# machine_io.net
KiCad netlist of a schematic drawn in Altium Designer
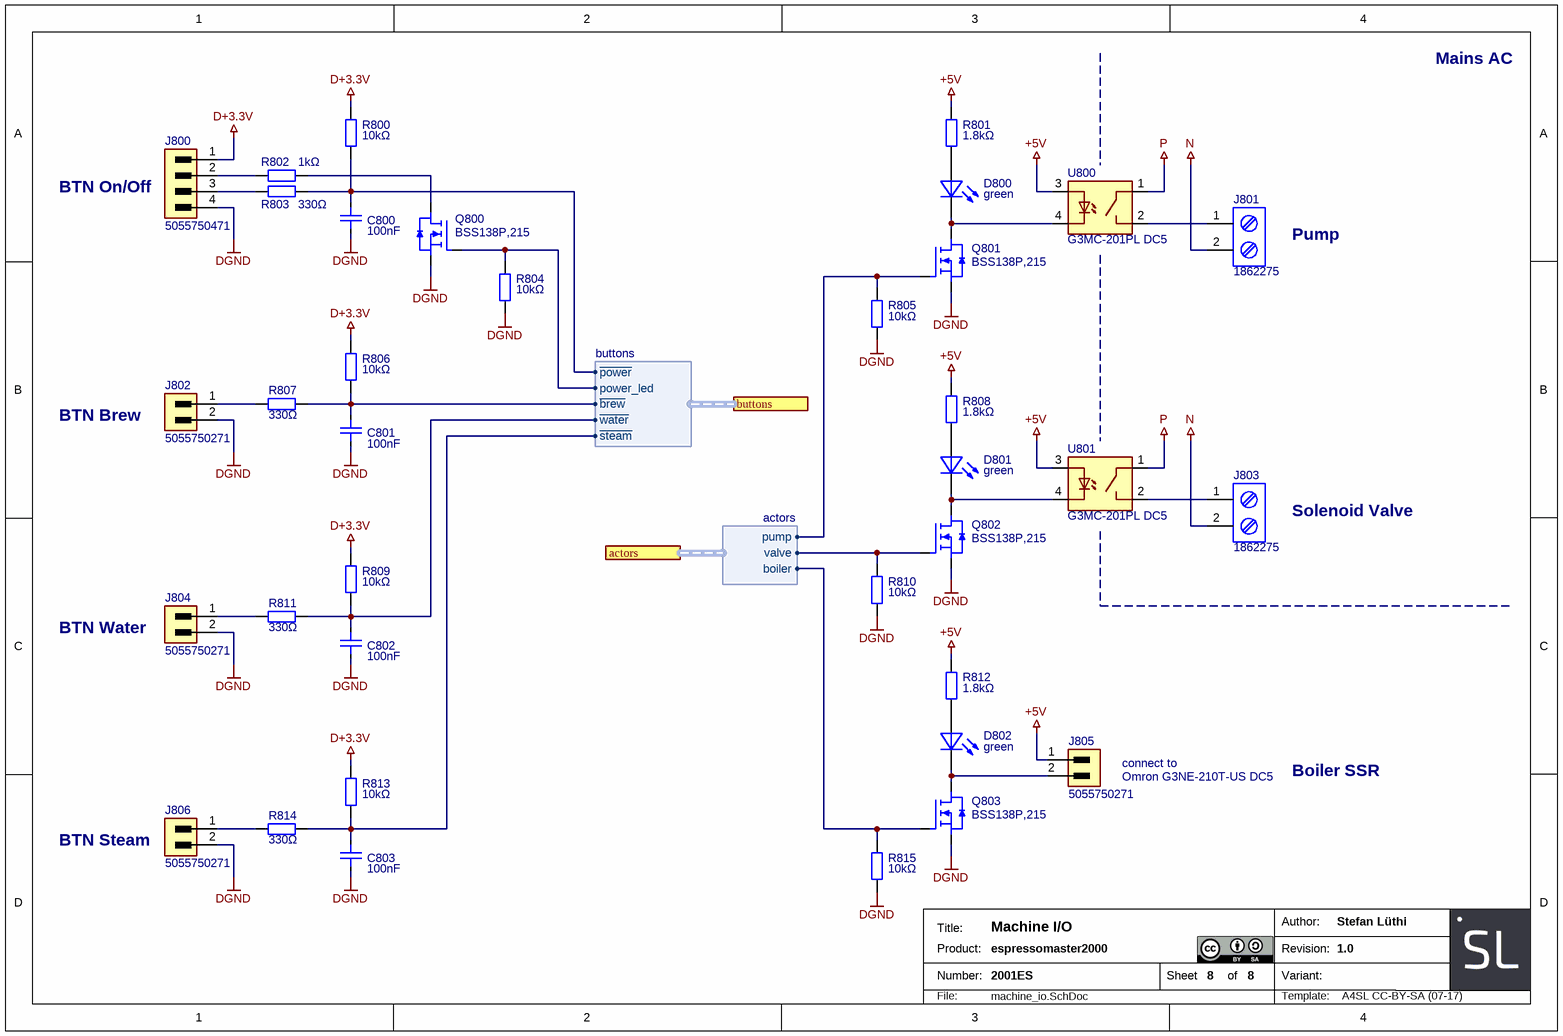
[diagram p0: machine_io.SchDoc]

(export (version "E")
  (design (tool "Eeschema 10.0.6"))
  (components
    (comp (ref "C800")
      (value "100nF")
      (footprint "SMD0603CAP")
      (description "Ceramic Capacitor")
      (libsource (lib "SL-Library") (part "Capacitor Ceramic"))
    )
    (comp (ref "C801")
      (value "100nF")
      (footprint "SMD0603CAP")
      (description "Ceramic Capacitor")
      (libsource (lib "SL-Library") (part "Capacitor Ceramic"))
    )
    (comp (ref "C802")
      (value "100nF")
      (footprint "SMD0603CAP")
      (description "Ceramic Capacitor")
      (libsource (lib "SL-Library") (part "Capacitor Ceramic"))
    )
    (comp (ref "C803")
      (value "100nF")
      (footprint "SMD0603CAP")
      (description "Ceramic Capacitor")
      (libsource (lib "SL-Library") (part "Capacitor Ceramic"))
    )
    (comp (ref "D800")
      (value "green")
      (footprint "SMD0603LED")
      (description "LED")
      (libsource (lib "SL-Library") (part "LED"))
    )
    (comp (ref "D801")
      (value "green")
      (footprint "SMD0603LED")
      (description "LED")
      (libsource (lib "SL-Library") (part "LED"))
    )
    (comp (ref "D802")
      (value "green")
      (footprint "SMD0603LED")
      (description "LED")
      (libsource (lib "SL-Library") (part "LED"))
    )
    (comp (ref "J800")
      (value "5055750471")
      (footprint "5055750471")
      (description "Connector 4x1P")
      (libsource (lib "SL-Library") (part "Connector 4x1P"))
    )
    (comp (ref "J801")
      (value "1862275")
      (footprint "1862275")
      (description "Screw Terminal, 2 Position, 5mm Spacing")
      (libsource (lib "SL-Library") (part "1862275"))
    )
    (comp (ref "J802")
      (value "5055750271")
      (footprint "5055750271")
      (description "Connector 2x1P")
      (libsource (lib "SL-Library") (part "Connector 2x1P"))
    )
    (comp (ref "J803")
      (value "1862275")
      (footprint "1862275")
      (description "Screw Terminal, 2 Position, 5mm Spacing")
      (libsource (lib "SL-Library") (part "1862275"))
    )
    (comp (ref "J804")
      (value "5055750271")
      (footprint "5055750271")
      (description "Connector 2x1P")
      (libsource (lib "SL-Library") (part "Connector 2x1P"))
    )
    (comp (ref "J805")
      (value "5055750271")
      (footprint "5055750271")
      (description "Connector 2x1P")
      (libsource (lib "") (part "Connector 2x1P_1"))
    )
    (comp (ref "J806")
      (value "5055750271")
      (footprint "5055750271")
      (description "Connector 2x1P")
      (libsource (lib "SL-Library") (part "Connector 2x1P"))
    )
    (comp (ref "Q800")
      (value "BSS138P,215")
      (footprint "SOT-23-FET")
      (description "NMOS Transistor")
      (libsource (lib "SL-Library") (part "NMOS"))
    )
    (comp (ref "Q801")
      (value "BSS138P,215")
      (footprint "SOT-23-FET")
      (description "NMOS Transistor")
      (libsource (lib "SL-Library") (part "NMOS"))
    )
    (comp (ref "Q802")
      (value "BSS138P,215")
      (footprint "SOT-23-FET")
      (description "NMOS Transistor")
      (libsource (lib "SL-Library") (part "NMOS"))
    )
    (comp (ref "Q803")
      (value "BSS138P,215")
      (footprint "SOT-23-FET")
      (description "NMOS Transistor")
      (libsource (lib "SL-Library") (part "NMOS"))
    )
    (comp (ref "R800")
      (value "10kΩ")
      (footprint "SMD0603RES")
      (description "Resistor")
      (libsource (lib "SL-Library") (part "Resistor"))
    )
    (comp (ref "R801")
      (value "1.8kΩ")
      (footprint "SMD0603RES")
      (description "Resistor")
      (libsource (lib "SL-Library") (part "Resistor"))
    )
    (comp (ref "R802")
      (value "1kΩ")
      (footprint "SMD0603RES")
      (description "Resistor")
      (libsource (lib "") (part "Resistor_2"))
    )
    (comp (ref "R803")
      (value "330Ω")
      (footprint "SMD0603RES")
      (description "Resistor")
      (libsource (lib "") (part "Resistor_1"))
    )
    (comp (ref "R804")
      (value "10kΩ")
      (footprint "SMD0603RES")
      (description "Resistor")
      (libsource (lib "") (part "Resistor_1"))
    )
    (comp (ref "R805")
      (value "10kΩ")
      (footprint "SMD0603RES")
      (description "Resistor")
      (libsource (lib "") (part "Resistor_2"))
    )
    (comp (ref "R806")
      (value "10kΩ")
      (footprint "SMD0603RES")
      (description "Resistor")
      (libsource (lib "SL-Library") (part "Resistor"))
    )
    (comp (ref "R807")
      (value "330Ω")
      (footprint "SMD0603RES")
      (description "Resistor")
      (libsource (lib "") (part "Resistor_1"))
    )
    (comp (ref "R808")
      (value "1.8kΩ")
      (footprint "SMD0603RES")
      (description "Resistor")
      (libsource (lib "SL-Library") (part "Resistor"))
    )
    (comp (ref "R809")
      (value "10kΩ")
      (footprint "SMD0603RES")
      (description "Resistor")
      (libsource (lib "SL-Library") (part "Resistor"))
    )
    (comp (ref "R810")
      (value "10kΩ")
      (footprint "SMD0603RES")
      (description "Resistor")
      (libsource (lib "") (part "Resistor_2"))
    )
    (comp (ref "R811")
      (value "330Ω")
      (footprint "SMD0603RES")
      (description "Resistor")
      (libsource (lib "") (part "Resistor_1"))
    )
    (comp (ref "R812")
      (value "1.8kΩ")
      (footprint "SMD0603RES")
      (description "Resistor")
      (libsource (lib "SL-Library") (part "Resistor"))
    )
    (comp (ref "R813")
      (value "10kΩ")
      (footprint "SMD0603RES")
      (description "Resistor")
      (libsource (lib "SL-Library") (part "Resistor"))
    )
    (comp (ref "R814")
      (value "330Ω")
      (footprint "SMD0603RES")
      (description "Resistor")
      (libsource (lib "") (part "Resistor_1"))
    )
    (comp (ref "R815")
      (value "10kΩ")
      (footprint "SMD0603RES")
      (description "Resistor")
      (libsource (lib "") (part "Resistor_2"))
    )
    (comp (ref "U800")
      (value "G3MC-201PL DC5")
      (footprint "G3MC-202P")
      (description "OptoMOS Solid State Relay")
      (libsource (lib "SL-Library") (part "OptoMOS SSR"))
    )
    (comp (ref "U801")
      (value "G3MC-201PL DC5")
      (footprint "G3MC-202P")
      (description "OptoMOS Solid State Relay")
      (libsource (lib "SL-Library") (part "OptoMOS SSR"))
    )
  )
  (nets
    (net (code "3") (name "+5V") (class "Default")
      (node (ref "J805") (pin "1") (pinfunction "1_1") (pintype "passive"))
      (node (ref "R801") (pin "2") (pinfunction "2_2") (pintype "passive"))
      (node (ref "R808") (pin "2") (pinfunction "2_2") (pintype "passive"))
      (node (ref "R812") (pin "2") (pinfunction "2_2") (pintype "passive"))
      (node (ref "U800") (pin "3") (pinfunction "3_3") (pintype "passive"))
      (node (ref "U801") (pin "3") (pinfunction "3_3") (pintype "passive"))
    )
    (net (code "6") (name "D+3.3V") (class "Default")
      (node (ref "J800") (pin "1") (pinfunction "1_1") (pintype "passive"))
      (node (ref "R800") (pin "2") (pinfunction "2_2") (pintype "passive"))
      (node (ref "R806") (pin "2") (pinfunction "2_2") (pintype "passive"))
      (node (ref "R809") (pin "2") (pinfunction "2_2") (pintype "passive"))
      (node (ref "R813") (pin "2") (pinfunction "2_2") (pintype "passive"))
    )
    (net (code "7") (name "DGND") (class "Default")
      (node (ref "C800") (pin "2") (pinfunction "2_2") (pintype "passive"))
      (node (ref "C801") (pin "2") (pinfunction "2_2") (pintype "passive"))
      (node (ref "C802") (pin "2") (pinfunction "2_2") (pintype "passive"))
      (node (ref "C803") (pin "2") (pinfunction "2_2") (pintype "passive"))
      (node (ref "J800") (pin "4") (pinfunction "4_4") (pintype "passive"))
      (node (ref "J802") (pin "2") (pinfunction "2_2") (pintype "passive"))
      (node (ref "J804") (pin "2") (pinfunction "2_2") (pintype "passive"))
      (node (ref "J806") (pin "2") (pinfunction "2_2") (pintype "passive"))
      (node (ref "Q800") (pin "S") (pinfunction "S_S") (pintype "passive"))
      (node (ref "Q801") (pin "S") (pinfunction "S_S") (pintype "passive"))
      (node (ref "Q802") (pin "S") (pinfunction "S_S") (pintype "passive"))
      (node (ref "Q803") (pin "S") (pinfunction "S_S") (pintype "passive"))
      (node (ref "R804") (pin "2") (pinfunction "2_2") (pintype "passive"))
      (node (ref "R805") (pin "2") (pinfunction "2_2") (pintype "passive"))
      (node (ref "R810") (pin "2") (pinfunction "2_2") (pintype "passive"))
      (node (ref "R815") (pin "2") (pinfunction "2_2") (pintype "passive"))
    )
    (net (code "8") (name "N") (class "Default")
      (node (ref "J801") (pin "2") (pinfunction "2_2") (pintype "passive"))
      (node (ref "J803") (pin "2") (pinfunction "2_2") (pintype "passive"))
    )
    (net (code "9") (name "Net-(C800-Pad1)") (class "Default")
      (node (ref "C800") (pin "1") (pinfunction "1_1") (pintype "passive"))
      (node (ref "R800") (pin "1") (pinfunction "1_1") (pintype "passive"))
      (node (ref "R803") (pin "1") (pinfunction "1_1") (pintype "passive"))
    )
    (net (code "10") (name "Net-(C801-Pad1)") (class "Default")
      (node (ref "C801") (pin "1") (pinfunction "1_1") (pintype "passive"))
      (node (ref "R806") (pin "1") (pinfunction "1_1") (pintype "passive"))
      (node (ref "R807") (pin "1") (pinfunction "1_1") (pintype "passive"))
    )
    (net (code "11") (name "Net-(C802-Pad1)") (class "Default")
      (node (ref "C802") (pin "1") (pinfunction "1_1") (pintype "passive"))
      (node (ref "R809") (pin "1") (pinfunction "1_1") (pintype "passive"))
      (node (ref "R811") (pin "1") (pinfunction "1_1") (pintype "passive"))
    )
    (net (code "12") (name "Net-(C803-Pad1)") (class "Default")
      (node (ref "C803") (pin "1") (pinfunction "1_1") (pintype "passive"))
      (node (ref "R813") (pin "1") (pinfunction "1_1") (pintype "passive"))
      (node (ref "R814") (pin "1") (pinfunction "1_1") (pintype "passive"))
    )
    (net (code "13") (name "Net-(D800-PadA)") (class "Default")
      (node (ref "D800") (pin "A") (pinfunction "A_A") (pintype "passive"))
      (node (ref "R801") (pin "1") (pinfunction "1_1") (pintype "passive"))
    )
    (net (code "14") (name "Net-(D800-PadC)") (class "Default")
      (node (ref "D800") (pin "C") (pinfunction "C_C") (pintype "passive"))
      (node (ref "Q801") (pin "D") (pinfunction "D_D") (pintype "passive"))
      (node (ref "U800") (pin "4") (pinfunction "4_4") (pintype "passive"))
    )
    (net (code "15") (name "Net-(D801-PadA)") (class "Default")
      (node (ref "D801") (pin "A") (pinfunction "A_A") (pintype "passive"))
      (node (ref "R808") (pin "1") (pinfunction "1_1") (pintype "passive"))
    )
    (net (code "16") (name "Net-(D801-PadC)") (class "Default")
      (node (ref "D801") (pin "C") (pinfunction "C_C") (pintype "passive"))
      (node (ref "Q802") (pin "D") (pinfunction "D_D") (pintype "passive"))
      (node (ref "U801") (pin "4") (pinfunction "4_4") (pintype "passive"))
    )
    (net (code "17") (name "Net-(D802-PadA)") (class "Default")
      (node (ref "D802") (pin "A") (pinfunction "A_A") (pintype "passive"))
      (node (ref "R812") (pin "1") (pinfunction "1_1") (pintype "passive"))
    )
    (net (code "18") (name "Net-(D802-PadC)") (class "Default")
      (node (ref "D802") (pin "C") (pinfunction "C_C") (pintype "passive"))
      (node (ref "J805") (pin "2") (pinfunction "2_2") (pintype "passive"))
      (node (ref "Q803") (pin "D") (pinfunction "D_D") (pintype "passive"))
    )
    (net (code "19") (name "Net-(J800-Pad2)") (class "Default")
      (node (ref "J800") (pin "2") (pinfunction "2_2") (pintype "passive"))
      (node (ref "R802") (pin "2") (pinfunction "2_2") (pintype "passive"))
    )
    (net (code "20") (name "Net-(J800-Pad3)") (class "Default")
      (node (ref "J800") (pin "3") (pinfunction "3_3") (pintype "passive"))
      (node (ref "R803") (pin "2") (pinfunction "2_2") (pintype "passive"))
    )
    (net (code "21") (name "Net-(J801-Pad1)") (class "Default")
      (node (ref "J801") (pin "1") (pinfunction "1_1") (pintype "passive"))
      (node (ref "U800") (pin "2") (pinfunction "2_2") (pintype "passive"))
    )
    (net (code "22") (name "Net-(J802-Pad1)") (class "Default")
      (node (ref "J802") (pin "1") (pinfunction "1_1") (pintype "passive"))
      (node (ref "R807") (pin "2") (pinfunction "2_2") (pintype "passive"))
    )
    (net (code "23") (name "Net-(J803-Pad1)") (class "Default")
      (node (ref "J803") (pin "1") (pinfunction "1_1") (pintype "passive"))
      (node (ref "U801") (pin "2") (pinfunction "2_2") (pintype "passive"))
    )
    (net (code "24") (name "Net-(J804-Pad1)") (class "Default")
      (node (ref "J804") (pin "1") (pinfunction "1_1") (pintype "passive"))
      (node (ref "R811") (pin "2") (pinfunction "2_2") (pintype "passive"))
    )
    (net (code "25") (name "Net-(J806-Pad1)") (class "Default")
      (node (ref "J806") (pin "1") (pinfunction "1_1") (pintype "passive"))
      (node (ref "R814") (pin "2") (pinfunction "2_2") (pintype "passive"))
    )
    (net (code "26") (name "Net-(Q800-PadD)") (class "Default")
      (node (ref "Q800") (pin "D") (pinfunction "D_D") (pintype "passive"))
      (node (ref "R802") (pin "1") (pinfunction "1_1") (pintype "passive"))
    )
    (net (code "27") (name "Net-(Q800-PadG)") (class "Default")
      (node (ref "Q800") (pin "G") (pinfunction "G_G") (pintype "passive"))
      (node (ref "R804") (pin "1") (pinfunction "1_1") (pintype "passive"))
    )
    (net (code "28") (name "Net-(Q801-PadG)") (class "Default")
      (node (ref "Q801") (pin "G") (pinfunction "G_G") (pintype "passive"))
      (node (ref "R805") (pin "1") (pinfunction "1_1") (pintype "passive"))
    )
    (net (code "29") (name "Net-(Q802-PadG)") (class "Default")
      (node (ref "Q802") (pin "G") (pinfunction "G_G") (pintype "passive"))
      (node (ref "R810") (pin "1") (pinfunction "1_1") (pintype "passive"))
    )
    (net (code "30") (name "Net-(Q803-PadG)") (class "Default")
      (node (ref "Q803") (pin "G") (pinfunction "G_G") (pintype "passive"))
      (node (ref "R815") (pin "1") (pinfunction "1_1") (pintype "passive"))
    )
    (net (code "31") (name "P") (class "Default")
      (node (ref "U800") (pin "1") (pinfunction "1_1") (pintype "passive"))
      (node (ref "U801") (pin "1") (pinfunction "1_1") (pintype "passive"))
    )
  )
)
